# Channel_Switcher.net
KiCad netlist of a schematic drawn in Altium Designer
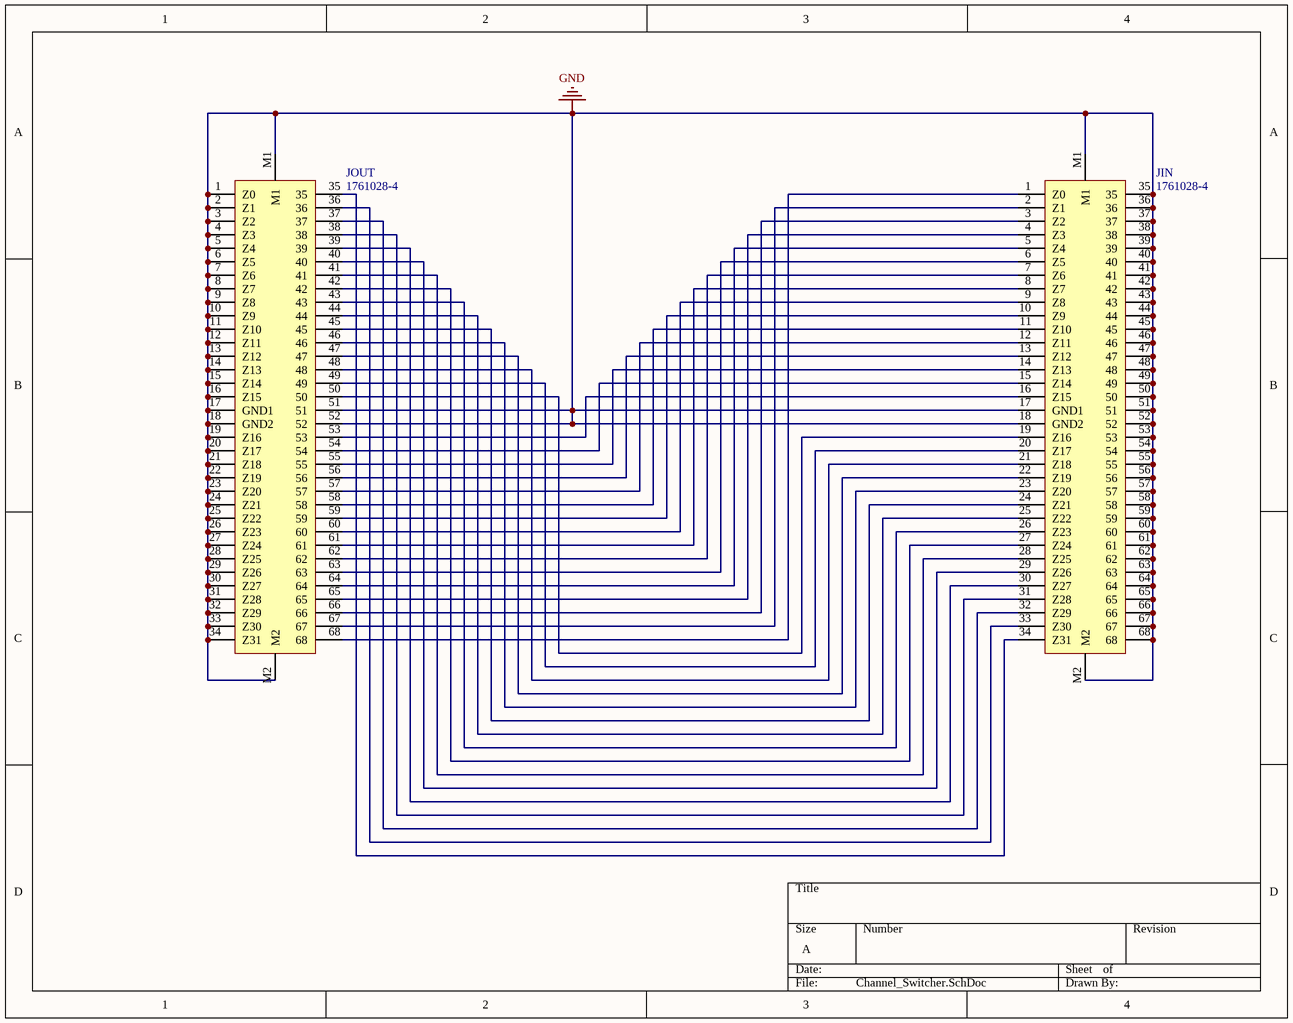
[diagram p0: Channel_Switcher.SchDoc]

(export (version "E")
  (design (tool "Eeschema 10.0.6"))
  (components
    (comp (ref "JIN")
      (value "1761028-4")
      (footprint "1761028-4-Footprint-1")
      (libsource (lib "Li-Ren Liu") (part "1761028-4-Symbol-1"))
    )
    (comp (ref "JOUT")
      (value "1761028-4")
      (footprint "1761028-4-Footprint-1")
      (libsource (lib "Li-Ren Liu") (part "1761028-4-Symbol-1"))
    )
  )
  (nets
    (net (code "1") (name "GND") (class "Default")
      (node (ref "JIN") (pin "17") (pinfunction "GND1_17") (pintype "passive"))
      (node (ref "JIN") (pin "18") (pinfunction "GND2_18") (pintype "passive"))
      (node (ref "JIN") (pin "35") (pinfunction "35_35") (pintype "passive"))
      (node (ref "JIN") (pin "36") (pinfunction "36_36") (pintype "passive"))
      (node (ref "JIN") (pin "37") (pinfunction "37_37") (pintype "passive"))
      (node (ref "JIN") (pin "38") (pinfunction "38_38") (pintype "passive"))
      (node (ref "JIN") (pin "39") (pinfunction "39_39") (pintype "passive"))
      (node (ref "JIN") (pin "40") (pinfunction "40_40") (pintype "passive"))
      (node (ref "JIN") (pin "41") (pinfunction "41_41") (pintype "passive"))
      (node (ref "JIN") (pin "42") (pinfunction "42_42") (pintype "passive"))
      (node (ref "JIN") (pin "43") (pinfunction "43_43") (pintype "passive"))
      (node (ref "JIN") (pin "44") (pinfunction "44_44") (pintype "passive"))
      (node (ref "JIN") (pin "45") (pinfunction "45_45") (pintype "passive"))
      (node (ref "JIN") (pin "46") (pinfunction "46_46") (pintype "passive"))
      (node (ref "JIN") (pin "47") (pinfunction "47_47") (pintype "passive"))
      (node (ref "JIN") (pin "48") (pinfunction "48_48") (pintype "passive"))
      (node (ref "JIN") (pin "49") (pinfunction "49_49") (pintype "passive"))
      (node (ref "JIN") (pin "50") (pinfunction "50_50") (pintype "passive"))
      (node (ref "JIN") (pin "51") (pinfunction "51_51") (pintype "passive"))
      (node (ref "JIN") (pin "52") (pinfunction "52_52") (pintype "passive"))
      (node (ref "JIN") (pin "53") (pinfunction "53_53") (pintype "passive"))
      (node (ref "JIN") (pin "54") (pinfunction "54_54") (pintype "passive"))
      (node (ref "JIN") (pin "55") (pinfunction "55_55") (pintype "passive"))
      (node (ref "JIN") (pin "56") (pinfunction "56_56") (pintype "passive"))
      (node (ref "JIN") (pin "57") (pinfunction "57_57") (pintype "passive"))
      (node (ref "JIN") (pin "58") (pinfunction "58_58") (pintype "passive"))
      (node (ref "JIN") (pin "59") (pinfunction "59_59") (pintype "passive"))
      (node (ref "JIN") (pin "60") (pinfunction "60_60") (pintype "passive"))
      (node (ref "JIN") (pin "61") (pinfunction "61_61") (pintype "passive"))
      (node (ref "JIN") (pin "62") (pinfunction "62_62") (pintype "passive"))
      (node (ref "JIN") (pin "63") (pinfunction "63_63") (pintype "passive"))
      (node (ref "JIN") (pin "64") (pinfunction "64_64") (pintype "passive"))
      (node (ref "JIN") (pin "65") (pinfunction "65_65") (pintype "passive"))
      (node (ref "JIN") (pin "66") (pinfunction "66_66") (pintype "passive"))
      (node (ref "JIN") (pin "67") (pinfunction "67_67") (pintype "passive"))
      (node (ref "JIN") (pin "68") (pinfunction "68_68") (pintype "passive"))
      (node (ref "JIN") (pin "M1") (pinfunction "M1_M1") (pintype "passive"))
      (node (ref "JIN") (pin "M2") (pinfunction "M2_M2") (pintype "passive"))
      (node (ref "JOUT") (pin "1") (pinfunction "Z0_1") (pintype "passive"))
      (node (ref "JOUT") (pin "10") (pinfunction "Z9_10") (pintype "passive"))
      (node (ref "JOUT") (pin "11") (pinfunction "Z10_11") (pintype "passive"))
      (node (ref "JOUT") (pin "12") (pinfunction "Z11_12") (pintype "passive"))
      (node (ref "JOUT") (pin "13") (pinfunction "Z12_13") (pintype "passive"))
      (node (ref "JOUT") (pin "14") (pinfunction "Z13_14") (pintype "passive"))
      (node (ref "JOUT") (pin "15") (pinfunction "Z14_15") (pintype "passive"))
      (node (ref "JOUT") (pin "16") (pinfunction "Z15_16") (pintype "passive"))
      (node (ref "JOUT") (pin "17") (pinfunction "GND1_17") (pintype "passive"))
      (node (ref "JOUT") (pin "18") (pinfunction "GND2_18") (pintype "passive"))
      (node (ref "JOUT") (pin "19") (pinfunction "Z16_19") (pintype "passive"))
      (node (ref "JOUT") (pin "2") (pinfunction "Z1_2") (pintype "passive"))
      (node (ref "JOUT") (pin "20") (pinfunction "Z17_20") (pintype "passive"))
      (node (ref "JOUT") (pin "21") (pinfunction "Z18_21") (pintype "passive"))
      (node (ref "JOUT") (pin "22") (pinfunction "Z19_22") (pintype "passive"))
      (node (ref "JOUT") (pin "23") (pinfunction "Z20_23") (pintype "passive"))
      (node (ref "JOUT") (pin "24") (pinfunction "Z21_24") (pintype "passive"))
      (node (ref "JOUT") (pin "25") (pinfunction "Z22_25") (pintype "passive"))
      (node (ref "JOUT") (pin "26") (pinfunction "Z23_26") (pintype "passive"))
      (node (ref "JOUT") (pin "27") (pinfunction "Z24_27") (pintype "passive"))
      (node (ref "JOUT") (pin "28") (pinfunction "Z25_28") (pintype "passive"))
      (node (ref "JOUT") (pin "29") (pinfunction "Z26_29") (pintype "passive"))
      (node (ref "JOUT") (pin "3") (pinfunction "Z2_3") (pintype "passive"))
      (node (ref "JOUT") (pin "30") (pinfunction "Z27_30") (pintype "passive"))
      (node (ref "JOUT") (pin "31") (pinfunction "Z28_31") (pintype "passive"))
      (node (ref "JOUT") (pin "32") (pinfunction "Z29_32") (pintype "passive"))
      (node (ref "JOUT") (pin "33") (pinfunction "Z30_33") (pintype "passive"))
      (node (ref "JOUT") (pin "34") (pinfunction "Z31_34") (pintype "passive"))
      (node (ref "JOUT") (pin "4") (pinfunction "Z3_4") (pintype "passive"))
      (node (ref "JOUT") (pin "5") (pinfunction "Z4_5") (pintype "passive"))
      (node (ref "JOUT") (pin "51") (pinfunction "51_51") (pintype "passive"))
      (node (ref "JOUT") (pin "52") (pinfunction "52_52") (pintype "passive"))
      (node (ref "JOUT") (pin "6") (pinfunction "Z5_6") (pintype "passive"))
      (node (ref "JOUT") (pin "7") (pinfunction "Z6_7") (pintype "passive"))
      (node (ref "JOUT") (pin "8") (pinfunction "Z7_8") (pintype "passive"))
      (node (ref "JOUT") (pin "9") (pinfunction "Z8_9") (pintype "passive"))
      (node (ref "JOUT") (pin "M1") (pinfunction "M1_M1") (pintype "passive"))
      (node (ref "JOUT") (pin "M2") (pinfunction "M2_M2") (pintype "passive"))
    )
    (net (code "2") (name "Net-(JIN-Z0)") (class "Default")
      (node (ref "JIN") (pin "1") (pinfunction "Z0_1") (pintype "passive"))
      (node (ref "JOUT") (pin "68") (pinfunction "68_68") (pintype "passive"))
    )
    (net (code "3") (name "Net-(JIN-Z1)") (class "Default")
      (node (ref "JIN") (pin "2") (pinfunction "Z1_2") (pintype "passive"))
      (node (ref "JOUT") (pin "67") (pinfunction "67_67") (pintype "passive"))
    )
    (net (code "4") (name "Net-(JIN-Z2)") (class "Default")
      (node (ref "JIN") (pin "3") (pinfunction "Z2_3") (pintype "passive"))
      (node (ref "JOUT") (pin "66") (pinfunction "66_66") (pintype "passive"))
    )
    (net (code "5") (name "Net-(JIN-Z3)") (class "Default")
      (node (ref "JIN") (pin "4") (pinfunction "Z3_4") (pintype "passive"))
      (node (ref "JOUT") (pin "65") (pinfunction "65_65") (pintype "passive"))
    )
    (net (code "6") (name "Net-(JIN-Z4)") (class "Default")
      (node (ref "JIN") (pin "5") (pinfunction "Z4_5") (pintype "passive"))
      (node (ref "JOUT") (pin "64") (pinfunction "64_64") (pintype "passive"))
    )
    (net (code "7") (name "Net-(JIN-Z5)") (class "Default")
      (node (ref "JIN") (pin "6") (pinfunction "Z5_6") (pintype "passive"))
      (node (ref "JOUT") (pin "63") (pinfunction "63_63") (pintype "passive"))
    )
    (net (code "8") (name "Net-(JIN-Z6)") (class "Default")
      (node (ref "JIN") (pin "7") (pinfunction "Z6_7") (pintype "passive"))
      (node (ref "JOUT") (pin "62") (pinfunction "62_62") (pintype "passive"))
    )
    (net (code "9") (name "Net-(JIN-Z7)") (class "Default")
      (node (ref "JIN") (pin "8") (pinfunction "Z7_8") (pintype "passive"))
      (node (ref "JOUT") (pin "61") (pinfunction "61_61") (pintype "passive"))
    )
    (net (code "10") (name "Net-(JIN-Z8)") (class "Default")
      (node (ref "JIN") (pin "9") (pinfunction "Z8_9") (pintype "passive"))
      (node (ref "JOUT") (pin "60") (pinfunction "60_60") (pintype "passive"))
    )
    (net (code "11") (name "Net-(JIN-Z9)") (class "Default")
      (node (ref "JIN") (pin "10") (pinfunction "Z9_10") (pintype "passive"))
      (node (ref "JOUT") (pin "59") (pinfunction "59_59") (pintype "passive"))
    )
    (net (code "12") (name "Net-(JIN-Z10)") (class "Default")
      (node (ref "JIN") (pin "11") (pinfunction "Z10_11") (pintype "passive"))
      (node (ref "JOUT") (pin "58") (pinfunction "58_58") (pintype "passive"))
    )
    (net (code "13") (name "Net-(JIN-Z11)") (class "Default")
      (node (ref "JIN") (pin "12") (pinfunction "Z11_12") (pintype "passive"))
      (node (ref "JOUT") (pin "57") (pinfunction "57_57") (pintype "passive"))
    )
    (net (code "14") (name "Net-(JIN-Z12)") (class "Default")
      (node (ref "JIN") (pin "13") (pinfunction "Z12_13") (pintype "passive"))
      (node (ref "JOUT") (pin "56") (pinfunction "56_56") (pintype "passive"))
    )
    (net (code "15") (name "Net-(JIN-Z13)") (class "Default")
      (node (ref "JIN") (pin "14") (pinfunction "Z13_14") (pintype "passive"))
      (node (ref "JOUT") (pin "55") (pinfunction "55_55") (pintype "passive"))
    )
    (net (code "16") (name "Net-(JIN-Z14)") (class "Default")
      (node (ref "JIN") (pin "15") (pinfunction "Z14_15") (pintype "passive"))
      (node (ref "JOUT") (pin "54") (pinfunction "54_54") (pintype "passive"))
    )
    (net (code "17") (name "Net-(JIN-Z15)") (class "Default")
      (node (ref "JIN") (pin "16") (pinfunction "Z15_16") (pintype "passive"))
      (node (ref "JOUT") (pin "53") (pinfunction "53_53") (pintype "passive"))
    )
    (net (code "18") (name "Net-(JIN-Z16)") (class "Default")
      (node (ref "JIN") (pin "19") (pinfunction "Z16_19") (pintype "passive"))
      (node (ref "JOUT") (pin "50") (pinfunction "50_50") (pintype "passive"))
    )
    (net (code "19") (name "Net-(JIN-Z17)") (class "Default")
      (node (ref "JIN") (pin "20") (pinfunction "Z17_20") (pintype "passive"))
      (node (ref "JOUT") (pin "49") (pinfunction "49_49") (pintype "passive"))
    )
    (net (code "20") (name "Net-(JIN-Z18)") (class "Default")
      (node (ref "JIN") (pin "21") (pinfunction "Z18_21") (pintype "passive"))
      (node (ref "JOUT") (pin "48") (pinfunction "48_48") (pintype "passive"))
    )
    (net (code "21") (name "Net-(JIN-Z19)") (class "Default")
      (node (ref "JIN") (pin "22") (pinfunction "Z19_22") (pintype "passive"))
      (node (ref "JOUT") (pin "47") (pinfunction "47_47") (pintype "passive"))
    )
    (net (code "22") (name "Net-(JIN-Z20)") (class "Default")
      (node (ref "JIN") (pin "23") (pinfunction "Z20_23") (pintype "passive"))
      (node (ref "JOUT") (pin "46") (pinfunction "46_46") (pintype "passive"))
    )
    (net (code "23") (name "Net-(JIN-Z21)") (class "Default")
      (node (ref "JIN") (pin "24") (pinfunction "Z21_24") (pintype "passive"))
      (node (ref "JOUT") (pin "45") (pinfunction "45_45") (pintype "passive"))
    )
    (net (code "24") (name "Net-(JIN-Z22)") (class "Default")
      (node (ref "JIN") (pin "25") (pinfunction "Z22_25") (pintype "passive"))
      (node (ref "JOUT") (pin "44") (pinfunction "44_44") (pintype "passive"))
    )
    (net (code "25") (name "Net-(JIN-Z23)") (class "Default")
      (node (ref "JIN") (pin "26") (pinfunction "Z23_26") (pintype "passive"))
      (node (ref "JOUT") (pin "43") (pinfunction "43_43") (pintype "passive"))
    )
    (net (code "26") (name "Net-(JIN-Z24)") (class "Default")
      (node (ref "JIN") (pin "27") (pinfunction "Z24_27") (pintype "passive"))
      (node (ref "JOUT") (pin "42") (pinfunction "42_42") (pintype "passive"))
    )
    (net (code "27") (name "Net-(JIN-Z25)") (class "Default")
      (node (ref "JIN") (pin "28") (pinfunction "Z25_28") (pintype "passive"))
      (node (ref "JOUT") (pin "41") (pinfunction "41_41") (pintype "passive"))
    )
    (net (code "28") (name "Net-(JIN-Z26)") (class "Default")
      (node (ref "JIN") (pin "29") (pinfunction "Z26_29") (pintype "passive"))
      (node (ref "JOUT") (pin "40") (pinfunction "40_40") (pintype "passive"))
    )
    (net (code "29") (name "Net-(JIN-Z27)") (class "Default")
      (node (ref "JIN") (pin "30") (pinfunction "Z27_30") (pintype "passive"))
      (node (ref "JOUT") (pin "39") (pinfunction "39_39") (pintype "passive"))
    )
    (net (code "30") (name "Net-(JIN-Z28)") (class "Default")
      (node (ref "JIN") (pin "31") (pinfunction "Z28_31") (pintype "passive"))
      (node (ref "JOUT") (pin "38") (pinfunction "38_38") (pintype "passive"))
    )
    (net (code "31") (name "Net-(JIN-Z29)") (class "Default")
      (node (ref "JIN") (pin "32") (pinfunction "Z29_32") (pintype "passive"))
      (node (ref "JOUT") (pin "37") (pinfunction "37_37") (pintype "passive"))
    )
    (net (code "32") (name "Net-(JIN-Z30)") (class "Default")
      (node (ref "JIN") (pin "33") (pinfunction "Z30_33") (pintype "passive"))
      (node (ref "JOUT") (pin "36") (pinfunction "36_36") (pintype "passive"))
    )
    (net (code "33") (name "Net-(JIN-Z31)") (class "Default")
      (node (ref "JIN") (pin "34") (pinfunction "Z31_34") (pintype "passive"))
      (node (ref "JOUT") (pin "35") (pinfunction "35_35") (pintype "passive"))
    )
  )
)
